# Fri3D_2026_01.net
KiCad netlist of a schematic drawn in Altium Designer
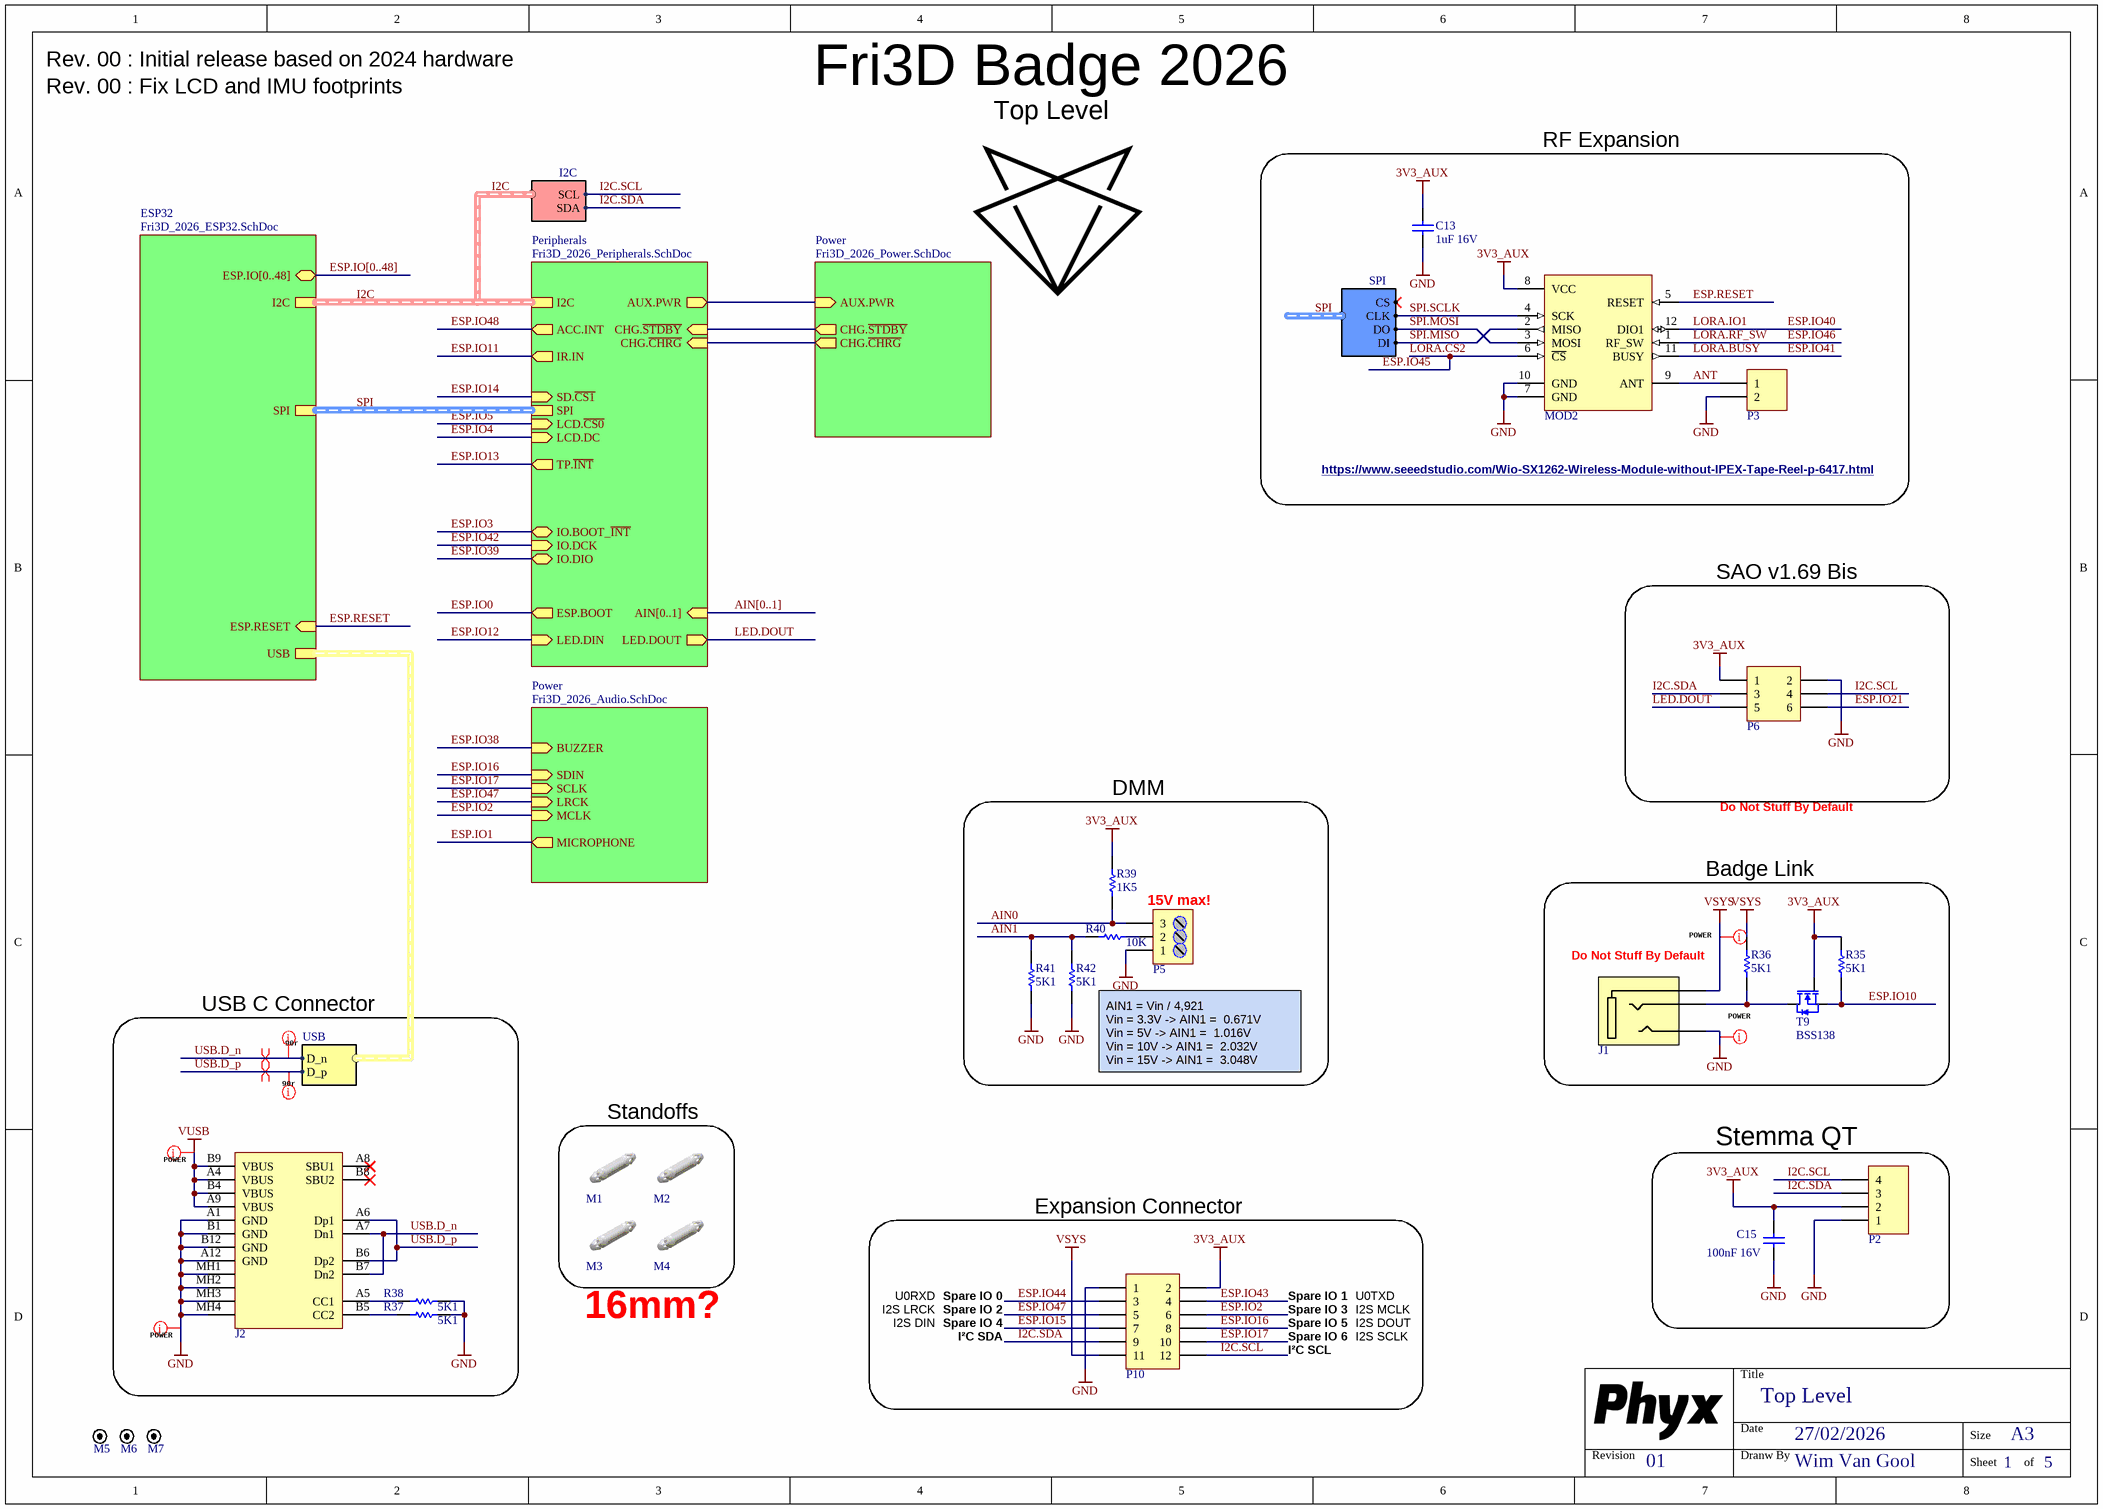
[diagram p0: Fri3D_2026_01.SchDoc]

(export (version "E")
  (design (tool "Eeschema 10.0.6"))
  (components
    (comp (ref "C13")
      (value "1uF 16V")
      (footprint "C0603_N")
      (description "Capacitor Ceramic")
      (libsource (lib "Phyx_Components") (part "CAP_CERAMIC"))
    )
    (comp (ref "C15")
      (value "100nF 16V")
      (footprint "C0603_N")
      (description "Capacitor Ceramic")
      (libsource (lib "Phyx_Components") (part "CAP_CERAMIC"))
    )
    (comp (ref "J1")
      (value "3.5mm jack, black, 3 contacts")
      (footprint "SHOU_HAN_PJ-320A-3P")
      (description "=Description")
      (libsource (lib "Phyx_Components") (part "AUDIO_RST-123"))
    )
    (comp (ref "J2")
      (value "USB 2.0 C Reversible Receptacle Horizontal full SMD")
      (footprint "XUNPU-TYPEC-304S-ACP16")
      (libsource (lib "Phyx_Components") (part "USB_C_16_4"))
    )
    (comp (ref "M1")
      (value "HIWA LCC-12 Snap-in - Snap-in 12.7mm")
      (footprint "WE_709622400")
      (libsource (lib "Phyx_Components") (part "WE_SNSN"))
    )
    (comp (ref "M2")
      (value "HIWA LCC-12 Snap-in - Snap-in 12.7mm")
      (footprint "WE_709622400")
      (libsource (lib "Phyx_Components") (part "WE_SNSN"))
    )
    (comp (ref "M3")
      (value "HIWA LCC-12 Snap-in - Snap-in 12.7mm")
      (footprint "WE_709622400")
      (libsource (lib "Phyx_Components") (part "WE_SNSN"))
    )
    (comp (ref "M4")
      (value "HIWA LCC-12 Snap-in - Snap-in 12.7mm")
      (footprint "WE_709622400")
      (libsource (lib "Phyx_Components") (part "WE_SNSN"))
    )
    (comp (ref "M5")
      (value "Fiducial 0.5mm")
      (footprint "FID_0.5mm")
      (description "FIDUCIAL")
      (libsource (lib "Phyx_Components") (part "FIDUCIAL"))
    )
    (comp (ref "M6")
      (value "Fiducial 0.5mm")
      (footprint "FID_0.5mm")
      (description "FIDUCIAL")
      (libsource (lib "Phyx_Components") (part "FIDUCIAL"))
    )
    (comp (ref "M7")
      (value "Fiducial 0.5mm")
      (footprint "FID_0.5mm")
      (description "FIDUCIAL")
      (libsource (lib "Phyx_Components") (part "FIDUCIAL"))
    )
    (comp (ref "MOD2")
      (value "868/915MHz 22dBm LoRa Module with Antenna Pin")
      (footprint "SEE_Wio-SX1262")
      (description "=Description")
      (libsource (lib "Phyx_Components") (part "SEE_Wio-SX1262"))
    )
    (comp (ref "P2")
      (value "Header 1.0mm RA Shrouded 4")
      (footprint "WE_665104131822")
      (libsource (lib "Phyx_Components") (part "Header 4"))
    )
    (comp (ref "P3")
      (value "DEALON DL-SMA-K513-08K")
      (footprint "DEA_DL-SMA-K513-08K")
      (libsource (lib "Phyx_Components") (part "Header 2"))
    )
    (comp (ref "P5")
      (value "3 Way Screw HDR 3.5mm Rising Cage")
      (footprint "WE_691103110003")
      (libsource (lib "Phyx_Components") (part "TERM_BLCK_3"))
    )
    (comp (ref "P6")
      (value "Receptacle 3x2")
      (footprint "RCPT2X3")
      (libsource (lib "Phyx_Components") (part "Header 3X2"))
    )
    (comp (ref "P10")
      (value "Receptacle 6x2 SMD low profile")
      (footprint "WE_610312243021_POST")
      (libsource (lib "Phyx_Components") (part "Header 6X2"))
    )
    (comp (ref "R35")
      (value "5K1")
      (footprint "R0603_N")
      (libsource (lib "Phyx_Components") (part "RESISTOR"))
    )
    (comp (ref "R36")
      (value "5K1")
      (footprint "R0603_N")
      (libsource (lib "Phyx_Components") (part "RESISTOR"))
    )
    (comp (ref "R37")
      (value "5K1")
      (footprint "R0603_N")
      (libsource (lib "Phyx_Components") (part "RESISTOR"))
    )
    (comp (ref "R38")
      (value "5K1")
      (footprint "R0603_N")
      (libsource (lib "Phyx_Components") (part "RESISTOR"))
    )
    (comp (ref "R39")
      (value "1K5")
      (footprint "R0603_N")
      (libsource (lib "Phyx_Components") (part "RESISTOR"))
    )
    (comp (ref "R40")
      (value "10K")
      (footprint "R0603_N")
      (libsource (lib "Phyx_Components") (part "RESISTOR"))
    )
    (comp (ref "R41")
      (value "5K1")
      (footprint "R0603_N")
      (libsource (lib "Phyx_Components") (part "RESISTOR"))
    )
    (comp (ref "R42")
      (value "5K1")
      (footprint "R0603_N")
      (libsource (lib "Phyx_Components") (part "RESISTOR"))
    )
    (comp (ref "T9")
      (value "BSS138")
      (footprint "SOT23-3")
      (fields (field (name "Comment") "0.2A N-Ch MOSFET Vgs 3.2"))
      (libsource (lib "Phyx_Components") (part "N_MOSFET_GSD"))
    )
  )
  (nets
    (net (code "30") (name "/AIN0") (class "Default")
      (node (ref "P5") (pin "3") (pinfunction "3_3") (pintype "passive"))
      (node (ref "R39") (pin "1") (pinfunction "1_1") (pintype "passive"))
    )
    (net (code "31") (name "/AIN1") (class "Default")
      (node (ref "R40") (pin "1") (pinfunction "1_1") (pintype "passive"))
      (node (ref "R41") (pin "2") (pinfunction "2_2") (pintype "passive"))
      (node (ref "R42") (pin "2") (pinfunction "2_2") (pintype "passive"))
    )
    (net (code "33") (name "/ANT") (class "Default")
      (node (ref "MOD2") (pin "9") (pinfunction "ANT_9") (pintype "passive"))
      (node (ref "P3") (pin "1") (pinfunction "1_1") (pintype "passive"))
    )
    (net (code "39") (name "/ESP.IO2") (class "Default")
      (node (ref "P10") (pin "6") (pinfunction "6_6") (pintype "passive"))
    )
    (net (code "43") (name "/ESP.IO10") (class "Default")
      (node (ref "R35") (pin "2") (pinfunction "2_2") (pintype "passive"))
      (node (ref "T9") (pin "2") (pinfunction "S_2") (pintype "passive"))
    )
    (net (code "48") (name "/ESP.IO15") (class "Default")
      (node (ref "P10") (pin "7") (pinfunction "7_7") (pintype "passive"))
    )
    (net (code "49") (name "/ESP.IO16") (class "Default")
      (node (ref "P10") (pin "8") (pinfunction "8_8") (pintype "passive"))
    )
    (net (code "50") (name "/ESP.IO17") (class "Default")
      (node (ref "P10") (pin "10") (pinfunction "10_10") (pintype "passive"))
    )
    (net (code "51") (name "/ESP.IO21") (class "Default")
      (node (ref "P6") (pin "6") (pinfunction "6_6") (pintype "passive"))
    )
    (net (code "54") (name "/ESP.IO40") (class "Default")
      (node (ref "MOD2") (pin "12") (pinfunction "DIO1_12") (pintype "bidirectional"))
    )
    (net (code "55") (name "/ESP.IO41") (class "Default")
      (node (ref "MOD2") (pin "11") (pinfunction "BUSY_11") (pintype "output"))
    )
    (net (code "57") (name "/ESP.IO43") (class "Default")
      (node (ref "P10") (pin "4") (pinfunction "4_4") (pintype "passive"))
    )
    (net (code "58") (name "/ESP.IO44") (class "Default")
      (node (ref "P10") (pin "3") (pinfunction "3_3") (pintype "passive"))
    )
    (net (code "59") (name "/ESP.IO45") (class "Default")
      (node (ref "MOD2") (pin "6") (pinfunction "~{CS}_6") (pintype "input"))
    )
    (net (code "60") (name "/ESP.IO46") (class "Default")
      (node (ref "MOD2") (pin "1") (pinfunction "RF_SW_1") (pintype "input"))
    )
    (net (code "61") (name "/ESP.IO47") (class "Default")
      (node (ref "P10") (pin "5") (pinfunction "5_5") (pintype "passive"))
    )
    (net (code "64") (name "/ESP.RESET") (class "Default")
      (node (ref "MOD2") (pin "5") (pinfunction "RESET_5") (pintype "input"))
    )
    (net (code "65") (name "/I2C.SCL") (class "Default")
      (node (ref "P10") (pin "12") (pinfunction "12_12") (pintype "passive"))
      (node (ref "P2") (pin "4") (pinfunction "4_4") (pintype "passive"))
      (node (ref "P6") (pin "4") (pinfunction "4_4") (pintype "passive"))
    )
    (net (code "66") (name "/I2C.SDA") (class "Default")
      (node (ref "P10") (pin "9") (pinfunction "9_9") (pintype "passive"))
      (node (ref "P2") (pin "3") (pinfunction "3_3") (pintype "passive"))
      (node (ref "P6") (pin "3") (pinfunction "3_3") (pintype "passive"))
    )
    (net (code "68") (name "/LED.DOUT") (class "Default")
      (node (ref "P6") (pin "5") (pinfunction "5_5") (pintype "passive"))
    )
    (net (code "69") (name "/SPI.MISO") (class "Default")
      (node (ref "MOD2") (pin "2") (pinfunction "MISO_2") (pintype "output"))
    )
    (net (code "70") (name "/SPI.MOSI") (class "Default")
      (node (ref "MOD2") (pin "3") (pinfunction "MOSI_3") (pintype "input"))
    )
    (net (code "71") (name "/SPI.SCLK") (class "Default")
      (node (ref "MOD2") (pin "4") (pinfunction "SCK_4") (pintype "input"))
    )
    (net (code "73") (name "/USB.D_n") (class "Default")
      (node (ref "J2") (pin "A7") (pinfunction "Dn1_A7") (pintype "passive"))
      (node (ref "J2") (pin "B7") (pinfunction "Dn2_B7") (pintype "passive"))
    )
    (net (code "74") (name "/USB.D_p") (class "Default")
      (node (ref "J2") (pin "A6") (pinfunction "Dp1_A6") (pintype "passive"))
      (node (ref "J2") (pin "B6") (pinfunction "Dp2_B6") (pintype "passive"))
    )
    (net (code "78") (name "3V3_AUX") (class "Default")
      (node (ref "C13") (pin "1") (pinfunction "1_1") (pintype "passive"))
      (node (ref "C15") (pin "1") (pinfunction "1_1") (pintype "passive"))
      (node (ref "MOD2") (pin "8") (pinfunction "VCC_8") (pintype "power_in"))
      (node (ref "P10") (pin "2") (pinfunction "2_2") (pintype "passive"))
      (node (ref "P2") (pin "2") (pinfunction "2_2") (pintype "passive"))
      (node (ref "P6") (pin "1") (pinfunction "1_1") (pintype "passive"))
      (node (ref "R35") (pin "1") (pinfunction "1_1") (pintype "passive"))
      (node (ref "R39") (pin "2") (pinfunction "2_2") (pintype "passive"))
      (node (ref "T9") (pin "1") (pinfunction "G_1") (pintype "passive"))
    )
    (net (code "79") (name "GND") (class "Default")
      (node (ref "C13") (pin "2") (pinfunction "2_2") (pintype "passive"))
      (node (ref "C15") (pin "2") (pinfunction "2_2") (pintype "passive"))
      (node (ref "J1") (pin "2") (pinfunction "Tip_2") (pintype "passive"))
      (node (ref "J2") (pin "A1") (pinfunction "GND_A1") (pintype "passive"))
      (node (ref "J2") (pin "A12") (pinfunction "GND_A12") (pintype "passive"))
      (node (ref "J2") (pin "B1") (pinfunction "GND_B1") (pintype "passive"))
      (node (ref "J2") (pin "B12") (pinfunction "GND_B12") (pintype "passive"))
      (node (ref "J2") (pin "MH1") (pinfunction "Tab_MH1") (pintype "passive"))
      (node (ref "J2") (pin "MH2") (pinfunction "Tab_MH2") (pintype "passive"))
      (node (ref "J2") (pin "MH3") (pinfunction "Tab_MH3") (pintype "passive"))
      (node (ref "J2") (pin "MH4") (pinfunction "Tab_MH4") (pintype "passive"))
      (node (ref "MOD2") (pin "10") (pinfunction "GND_10") (pintype "power_in"))
      (node (ref "MOD2") (pin "7") (pinfunction "GND_7") (pintype "power_in"))
      (node (ref "P10") (pin "1") (pinfunction "1_1") (pintype "passive"))
      (node (ref "P2") (pin "1") (pinfunction "1_1") (pintype "passive"))
      (node (ref "P3") (pin "2") (pinfunction "2_2") (pintype "passive"))
      (node (ref "P5") (pin "1") (pinfunction "1_1") (pintype "passive"))
      (node (ref "P6") (pin "2") (pinfunction "2_2") (pintype "passive"))
      (node (ref "R37") (pin "2") (pinfunction "2_2") (pintype "passive"))
      (node (ref "R38") (pin "2") (pinfunction "2_2") (pintype "passive"))
      (node (ref "R41") (pin "1") (pinfunction "1_1") (pintype "passive"))
      (node (ref "R42") (pin "1") (pinfunction "1_1") (pintype "passive"))
    )
    (net (code "80") (name "Net-(J1-Ring)") (class "Default")
      (node (ref "J1") (pin "3") (pinfunction "Ring_3") (pintype "passive"))
      (node (ref "R36") (pin "2") (pinfunction "2_2") (pintype "passive"))
      (node (ref "T9") (pin "3") (pinfunction "D_3") (pintype "passive"))
    )
    (net (code "81") (name "Net-(J2-CC1)") (class "Default")
      (node (ref "J2") (pin "A5") (pinfunction "CC1_A5") (pintype "passive"))
      (node (ref "R38") (pin "1") (pinfunction "1_1") (pintype "passive"))
    )
    (net (code "82") (name "Net-(J2-CC2)") (class "Default")
      (node (ref "J2") (pin "B5") (pinfunction "CC2_B5") (pintype "passive"))
      (node (ref "R37") (pin "1") (pinfunction "1_1") (pintype "passive"))
    )
    (net (code "83") (name "Net-(P5-Pad2)") (class "Default")
      (node (ref "P5") (pin "2") (pinfunction "2_2") (pintype "passive"))
      (node (ref "R40") (pin "2") (pinfunction "2_2") (pintype "passive"))
    )
    (net (code "84") (name "VSYS") (class "Default")
      (node (ref "J1") (pin "1") (pinfunction "Sleeve_1") (pintype "passive"))
      (node (ref "P10") (pin "11") (pinfunction "11_11") (pintype "passive"))
      (node (ref "R36") (pin "1") (pinfunction "1_1") (pintype "passive"))
    )
    (net (code "85") (name "VUSB") (class "Default")
      (node (ref "J2") (pin "A4") (pinfunction "VBUS_A4") (pintype "passive"))
      (node (ref "J2") (pin "A9") (pinfunction "VBUS_A9") (pintype "passive"))
      (node (ref "J2") (pin "B4") (pinfunction "VBUS_B4") (pintype "passive"))
      (node (ref "J2") (pin "B9") (pinfunction "VBUS_B9") (pintype "passive"))
    )
    (net (code "86") (name "unconnected-(J2-SBU1-PadA8)") (class "Default")
      (node (ref "J2") (pin "A8") (pinfunction "SBU1_A8") (pintype "passive+no_connect"))
    )
    (net (code "87") (name "unconnected-(J2-SBU2-PadB8)") (class "Default")
      (node (ref "J2") (pin "B8") (pinfunction "SBU2_B8") (pintype "passive+no_connect"))
    )
  )
)
